# 2_LTE_1.net
KiCad netlist of a schematic drawn in Altium Designer
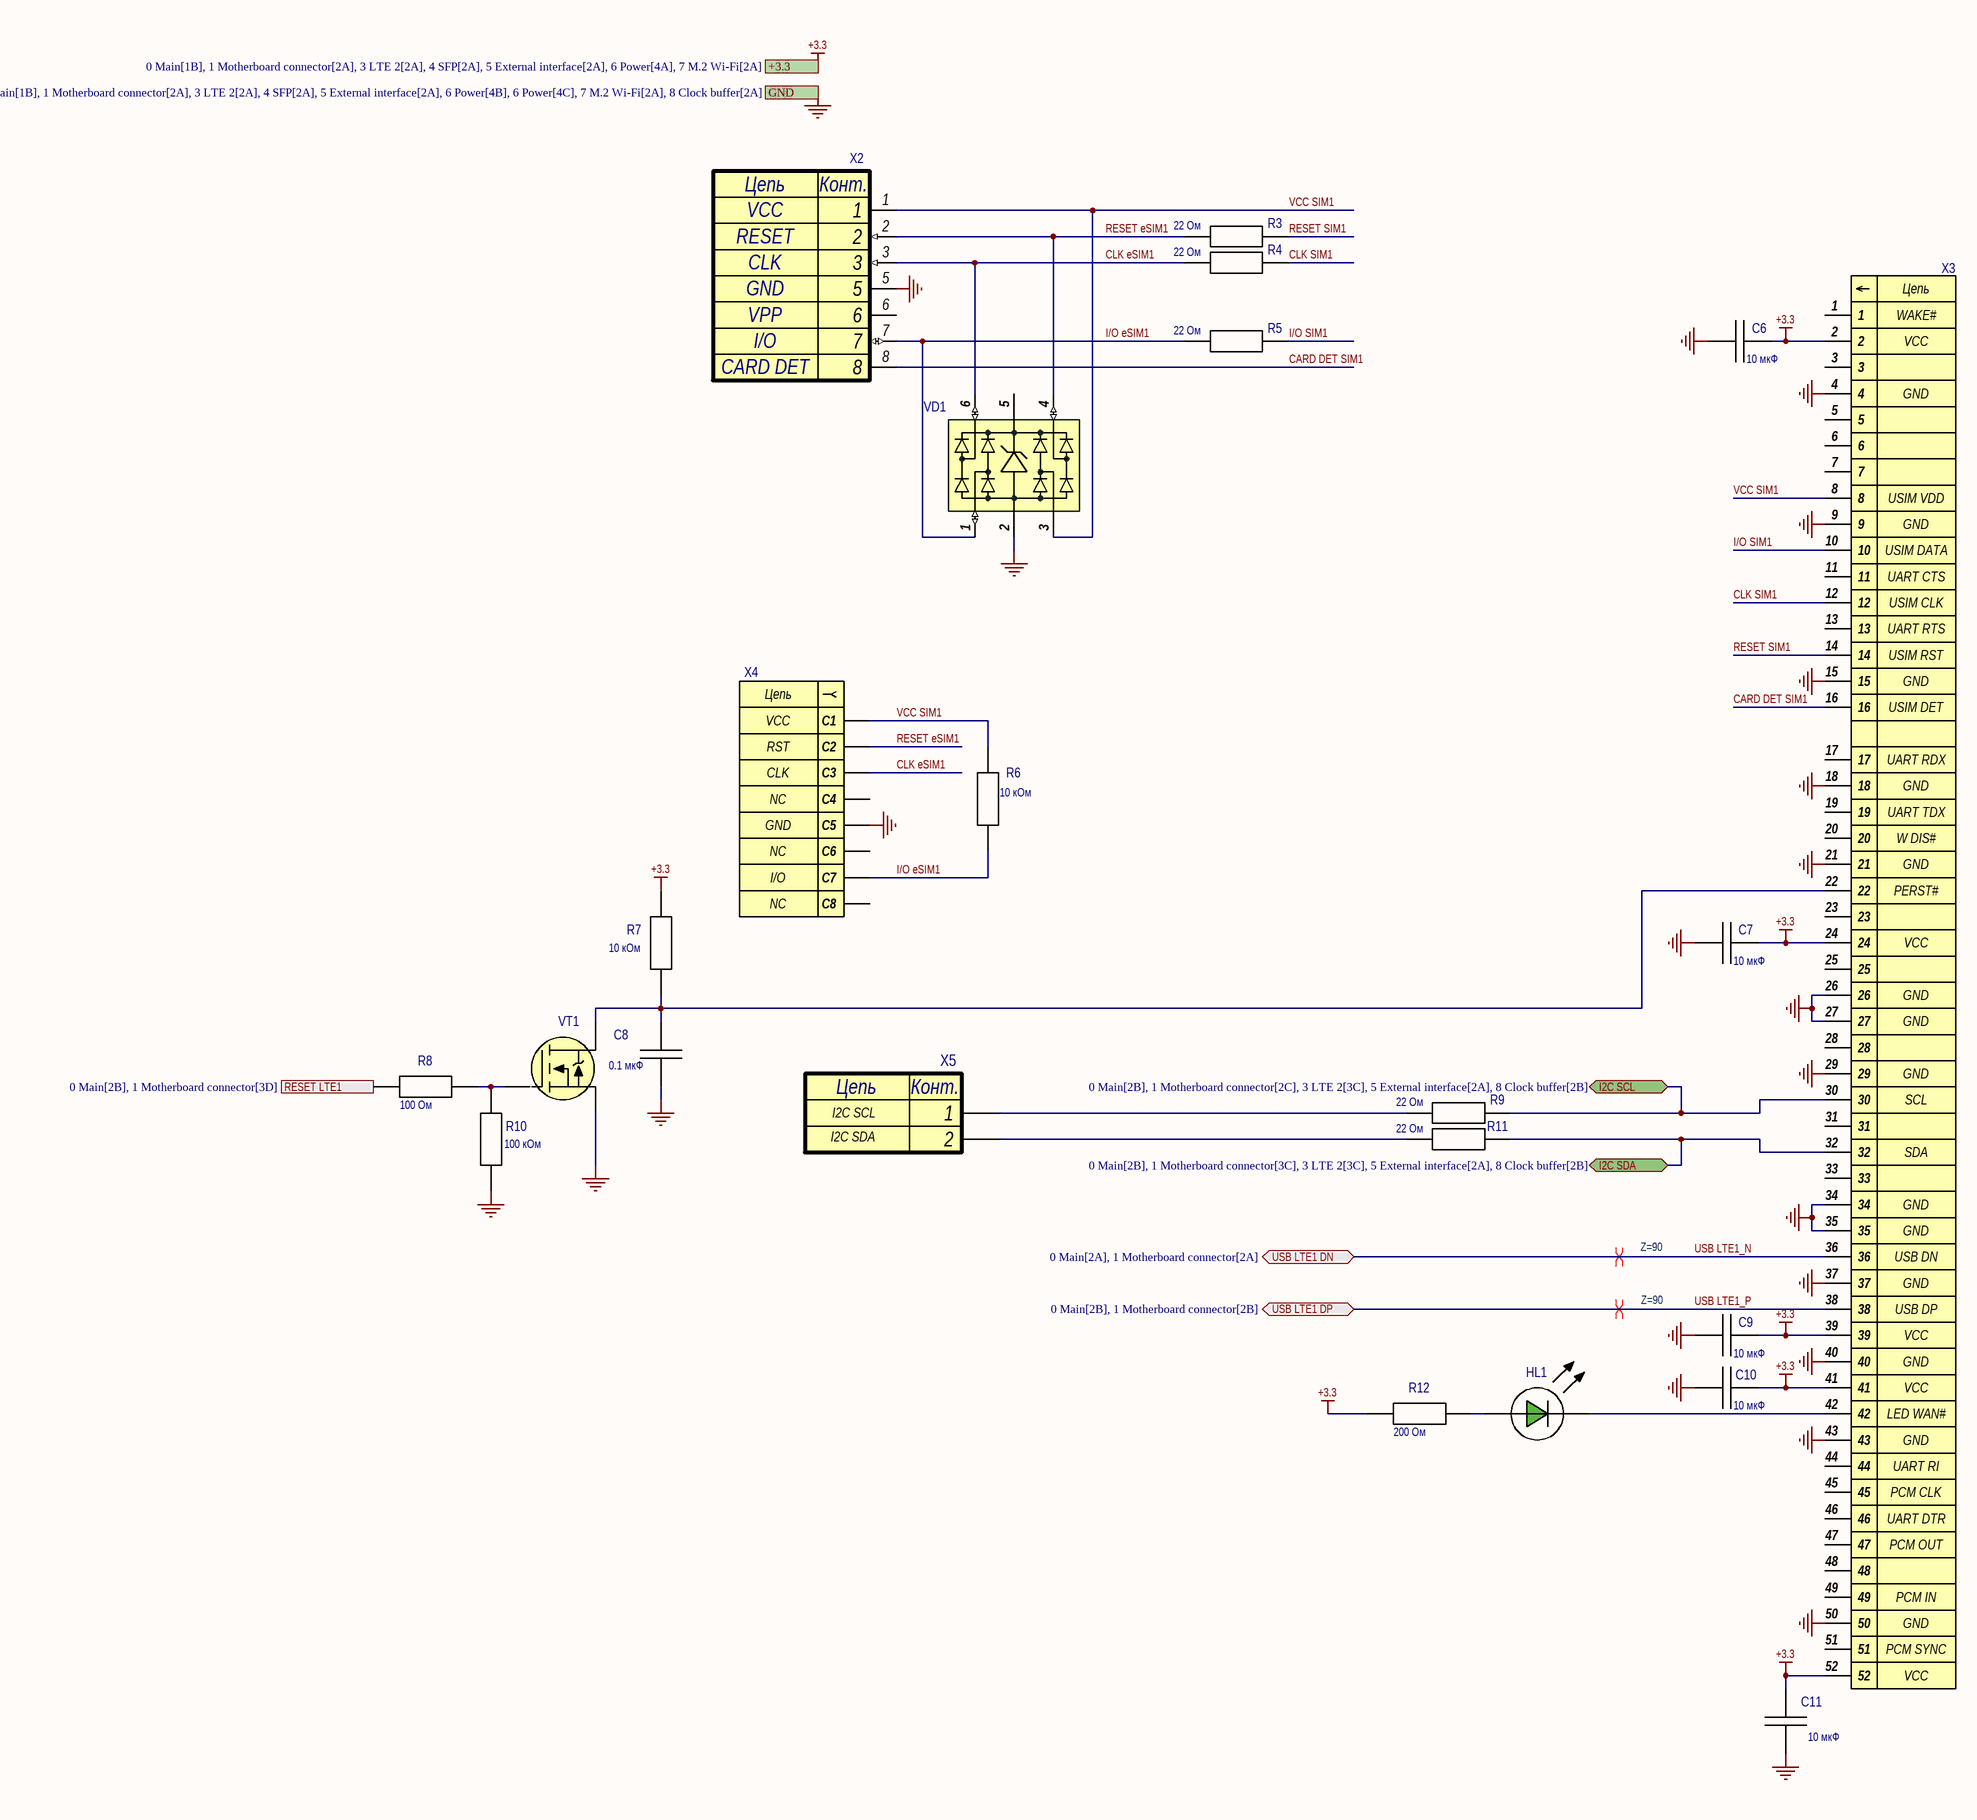
[diagram p0: 2 LTE 1.SchDoc]

(export (version "E")
  (design (tool "Eeschema 10.0.6"))
  (components
    (comp (ref "C6")
      (value "10 мкФ")
      (footprint "CAP_0805")
      (description "Конденсатор CHIP-0805 10 мкФ 16 В 10% X5R")
      (fields
        (field (name "PARTNUMBER") "GRM21BR61C106KE15L")
        (field (name "TOLERANCE") "10%")
        (field (name "AUTOR") "Цислав А.Н.")
      )
      (libsource (lib "Database_Altium") (part "STD_CAP"))
    )
    (comp (ref "C7")
      (value "10 мкФ")
      (footprint "CAP_0805")
      (description "Конденсатор CHIP-0805 10 мкФ 16 В 10% X5R")
      (fields
        (field (name "PARTNUMBER") "GRM21BR61C106KE15L")
        (field (name "TOLERANCE") "10%")
        (field (name "AUTOR") "Цислав А.Н.")
      )
      (libsource (lib "Database_Altium") (part "STD_CAP"))
    )
    (comp (ref "C8")
      (value "0.1 мкФ")
      (footprint "CAP_0402")
      (description "Конденсатор CHIP-0402 0.1 мкФ 50 В 10% X7R")
      (fields
        (field (name "PARTNUMBER") "CC0402KRX7R9BB104")
        (field (name "TOLERANCE") "10%")
        (field (name "AUTOR") "Admin")
      )
      (libsource (lib "Database_Altium") (part "STD_CAP"))
    )
    (comp (ref "C9")
      (value "10 мкФ")
      (footprint "CAP_0805")
      (description "Конденсатор CHIP-0805 10 мкФ 16 В 10% X5R")
      (fields
        (field (name "PARTNUMBER") "GRM21BR61C106KE15L")
        (field (name "TOLERANCE") "10%")
        (field (name "AUTOR") "Цислав А.Н.")
      )
      (libsource (lib "Database_Altium") (part "STD_CAP"))
    )
    (comp (ref "C10")
      (value "10 мкФ")
      (footprint "CAP_0805")
      (description "Конденсатор CHIP-0805 10 мкФ 16 В 10% X5R")
      (fields
        (field (name "PARTNUMBER") "GRM21BR61C106KE15L")
        (field (name "TOLERANCE") "10%")
        (field (name "AUTOR") "Цислав А.Н.")
      )
      (libsource (lib "Database_Altium") (part "STD_CAP"))
    )
    (comp (ref "C11")
      (value "10 мкФ")
      (footprint "CAP_0805")
      (description "Конденсатор CHIP-0805 10 мкФ 16 В 10% X5R")
      (fields
        (field (name "PARTNUMBER") "GRM21BR61C106KE15L")
        (field (name "TOLERANCE") "10%")
        (field (name "AUTOR") "Цислав А.Н.")
      )
      (libsource (lib "Database_Altium") (part "STD_CAP"))
    )
    (comp (ref "HL1")
      (value "APHHS1005CGCK")
      (footprint "LED_0402_GREEN")
      (description "Диод Kingbright 2 В 20 мА")
      (fields (field (name "MANUFACTURER") "Kingbright") (field (name "AUTOR") "Цислав А.Н."))
      (libsource (lib "Database_Altium") (part "APHHS1005CGCK"))
    )
    (comp (ref "R3")
      (value "22 Ом")
      (footprint "RES_0402")
      (description "Резистор CHIP-0402 22 Ом 1%")
      (fields
        (field (name "PARTNUMBER") "RC0402FR-0722RL")
        (field (name "TOLERANCE") "1%")
        (field (name "AUTOR") "Цислав А.Н.")
      )
      (libsource (lib "Database_Altium") (part "STD_RES"))
    )
    (comp (ref "R4")
      (value "22 Ом")
      (footprint "RES_0402")
      (description "Резистор CHIP-0402 22 Ом 1%")
      (fields
        (field (name "PARTNUMBER") "RC0402FR-0722RL")
        (field (name "TOLERANCE") "1%")
        (field (name "AUTOR") "Цислав А.Н.")
      )
      (libsource (lib "Database_Altium") (part "STD_RES"))
    )
    (comp (ref "R5")
      (value "22 Ом")
      (footprint "RES_0402")
      (description "Резистор CHIP-0402 22 Ом 1%")
      (fields
        (field (name "PARTNUMBER") "RC0402FR-0722RL")
        (field (name "TOLERANCE") "1%")
        (field (name "AUTOR") "Цислав А.Н.")
      )
      (libsource (lib "Database_Altium") (part "STD_RES"))
    )
    (comp (ref "R6")
      (value "10 кОм")
      (footprint "RES_0402")
      (description "Резистор CHIP-0402 10 кОм 5%")
      (fields
        (field (name "PARTNUMBER") "RC0402JR-0710KL")
        (field (name "TOLERANCE") "5%")
        (field (name "AUTOR") "Цислав А.Н.")
      )
      (libsource (lib "Database_Altium") (part "STD_RES"))
    )
    (comp (ref "R7")
      (value "10 кОм")
      (footprint "RES_0402")
      (description "Резистор CHIP-0402 10 кОм 5%")
      (fields
        (field (name "PARTNUMBER") "RC0402JR-0710KL")
        (field (name "TOLERANCE") "5%")
        (field (name "AUTOR") "Цислав А.Н.")
      )
      (libsource (lib "Database_Altium") (part "STD_RES"))
    )
    (comp (ref "R8")
      (value "100 Ом")
      (footprint "RES_0402")
      (description "Резистор CHIP-0402 100 Ом 5%")
      (fields
        (field (name "PARTNUMBER") "RC0402JR-07100RL")
        (field (name "TOLERANCE") "5%")
        (field (name "AUTOR") "Цислав А.Н.")
      )
      (libsource (lib "Database_Altium") (part "STD_RES"))
    )
    (comp (ref "R9")
      (value "22 Ом")
      (footprint "RES_0402")
      (description "Резистор CHIP-0402 22 Ом 1%")
      (fields
        (field (name "PARTNUMBER") "RC0402FR-0722RL")
        (field (name "TOLERANCE") "1%")
        (field (name "AUTOR") "Цислав А.Н.")
      )
      (libsource (lib "Database_Altium") (part "STD_RES"))
    )
    (comp (ref "R10")
      (value "100 кОм")
      (footprint "RES_0402")
      (description "Резистор CHIP-0402 100 кОм 5%")
      (fields
        (field (name "PARTNUMBER") "RC0402JR-07100KL")
        (field (name "TOLERANCE") "5%")
        (field (name "AUTOR") "Цислав А.Н.")
      )
      (libsource (lib "Database_Altium") (part "STD_RES"))
    )
    (comp (ref "R11")
      (value "22 Ом")
      (footprint "RES_0402")
      (description "Резистор CHIP-0402 22 Ом 1%")
      (fields
        (field (name "PARTNUMBER") "RC0402FR-0722RL")
        (field (name "TOLERANCE") "1%")
        (field (name "AUTOR") "Цислав А.Н.")
      )
      (libsource (lib "Database_Altium") (part "STD_RES"))
    )
    (comp (ref "R12")
      (value "200 Ом")
      (footprint "RES_0402")
      (description "Резистор CHIP-0402 200 Ом 5%")
      (fields
        (field (name "PARTNUMBER") "RC0402JR-07200RL")
        (field (name "TOLERANCE") "5%")
        (field (name "AUTOR") "Цислав А.Н.")
      )
      (libsource (lib "Database_Altium") (part "STD_RES"))
    )
    (comp (ref "VD1")
      (value "SRV05-4")
      (footprint "SOT-23-6")
      (description "Диод SEMTECH 1.2 В 12 А")
      (fields (field (name "MANUFACTURER") "SEMTECH") (field (name "AUTOR") "Admin"))
      (libsource (lib "Database_Altium") (part "SRV05-4"))
    )
    (comp (ref "VT1")
      (value "2N7002P")
      (footprint "SOT-23-3")
      (description "Микросхема NXP  N-channel Trench MOSFET")
      (fields
        (field (name "VOLTAGE") "60В")
        (field (name "MANUFACTURER") "NXP")
        (field (name "AUTOR") "Admin")
      )
      (libsource (lib "Database_Altium") (part "2N7002P"))
    )
    (comp (ref "X2")
      (value "Sim холдер с детектированием sim-card  и выдвижным держателем SMN-327-KT1B")
      (footprint "SMN-328-ACP7")
      (description "Разъем XunPu SIM")
      (fields
        (field (name "PARTNUMBER") "SMN-328-ACP7")
        (field (name "MANUFACTURER") "XunPu")
        (field (name "CONTACT") "8")
        (field (name "AUTOR") "Admin")
      )
      (libsource (lib "Database_Altium") (part "Sim WITH CD"))
    )
    (comp (ref "X3")
      (value "2041262-1")
      (footprint "2041262-1")
      (description "Разъем TE PCI-E")
      (fields (field (name "MANUFACTURER") "TE") (field (name "CONTACT") "52") (field (name "AUTOR") "Admin"))
      (libsource (lib "Database_Altium") (part "2041262-1"))
    )
    (comp (ref "X4")
      (value "SIM_MFF2")
      (footprint "SIM_MFF2")
      (description "Разъем E - SIM")
      (fields (field (name "MANUFACTURER") "E -") (field (name "CONTACT") "8") (field (name "AUTOR") "Admin"))
      (libsource (lib "Database_Altium") (part "SIM_MFF2"))
    )
    (comp (ref "X5")
      (value "STD_CON2")
      (footprint "PLS-2")
      (description "Разъем NoName PLS")
      (fields
        (field (name "PARTNUMBER") "PLS-2")
        (field (name "MANUFACTURER") "NoName")
        (field (name "CONTACT") "2")
        (field (name "AUTOR") "Admin")
      )
      (libsource (lib "Database_Altium") (part "STD_CON2"))
    )
  )
  (nets
    (net (code "1") (name "+3.3") (class "Default")
      (node (ref "C10") (pin "1") (pinfunction "1_1") (pintype "passive"))
      (node (ref "C11") (pin "1") (pinfunction "1_1") (pintype "passive"))
      (node (ref "C6") (pin "1") (pinfunction "1_1") (pintype "passive"))
      (node (ref "C7") (pin "1") (pinfunction "1_1") (pintype "passive"))
      (node (ref "C9") (pin "1") (pinfunction "1_1") (pintype "passive"))
      (node (ref "R12") (pin "1") (pinfunction "1_1") (pintype "passive"))
      (node (ref "R7") (pin "2") (pinfunction "2_2") (pintype "passive"))
      (node (ref "X3") (pin "2") (pinfunction "2_2") (pintype "passive"))
      (node (ref "X3") (pin "24") (pinfunction "24_24") (pintype "passive"))
      (node (ref "X3") (pin "39") (pinfunction "39_39") (pintype "passive"))
      (node (ref "X3") (pin "41") (pinfunction "41_41") (pintype "passive"))
      (node (ref "X3") (pin "52") (pinfunction "52_52") (pintype "passive"))
    )
    (net (code "2") (name "/CARD DET SIM1") (class "Default")
      (node (ref "X2") (pin "8") (pinfunction "8_8") (pintype "power_in"))
      (node (ref "X3") (pin "16") (pinfunction "16_16") (pintype "passive"))
    )
    (net (code "3") (name "/CLK SIM1") (class "Default")
      (node (ref "R4") (pin "2") (pinfunction "2_2") (pintype "passive"))
      (node (ref "X3") (pin "12") (pinfunction "12_12") (pintype "passive"))
    )
    (net (code "4") (name "/CLK eSIM1") (class "Default")
      (node (ref "R4") (pin "1") (pinfunction "1_1") (pintype "passive"))
      (node (ref "VD1") (pin "6") (pinfunction "6_6") (pintype "bidirectional"))
      (node (ref "X2") (pin "3") (pinfunction "3_3") (pintype "input"))
      (node (ref "X4") (pin "C3") (pinfunction "C3_C3") (pintype "passive"))
    )
    (net (code "5") (name "/I2C SCL") (class "Default")
      (node (ref "R9") (pin "2") (pinfunction "2_2") (pintype "passive"))
      (node (ref "X3") (pin "30") (pinfunction "30_30") (pintype "passive"))
    )
    (net (code "6") (name "/I2C SDA") (class "Default")
      (node (ref "R11") (pin "2") (pinfunction "2_2") (pintype "passive"))
      (node (ref "X3") (pin "32") (pinfunction "32_32") (pintype "passive"))
    )
    (net (code "7") (name "/I{slash}O SIM1") (class "Default")
      (node (ref "R5") (pin "2") (pinfunction "2_2") (pintype "passive"))
      (node (ref "X3") (pin "10") (pinfunction "10_10") (pintype "passive"))
    )
    (net (code "8") (name "/I{slash}O eSIM1") (class "Default")
      (node (ref "R5") (pin "1") (pinfunction "1_1") (pintype "passive"))
      (node (ref "R6") (pin "1") (pinfunction "1_1") (pintype "passive"))
      (node (ref "VD1") (pin "1") (pinfunction "1_1") (pintype "bidirectional"))
      (node (ref "X2") (pin "7") (pinfunction "7_7") (pintype "bidirectional"))
      (node (ref "X4") (pin "C7") (pinfunction "C7_C7") (pintype "passive"))
    )
    (net (code "9") (name "/RESET LTE1") (class "Default")
      (node (ref "R8") (pin "1") (pinfunction "1_1") (pintype "passive"))
    )
    (net (code "10") (name "/RESET SIM1") (class "Default")
      (node (ref "R3") (pin "2") (pinfunction "2_2") (pintype "passive"))
      (node (ref "X3") (pin "14") (pinfunction "14_14") (pintype "passive"))
    )
    (net (code "11") (name "/RESET eSIM1") (class "Default")
      (node (ref "R3") (pin "1") (pinfunction "1_1") (pintype "passive"))
      (node (ref "VD1") (pin "4") (pinfunction "4_4") (pintype "bidirectional"))
      (node (ref "X2") (pin "2") (pinfunction "2_2") (pintype "input"))
      (node (ref "X4") (pin "C2") (pinfunction "C2_C2") (pintype "passive"))
    )
    (net (code "12") (name "/USB LTE1_N") (class "Default")
      (node (ref "X3") (pin "36") (pinfunction "36_36") (pintype "passive"))
    )
    (net (code "13") (name "/USB LTE1_P") (class "Default")
      (node (ref "X3") (pin "38") (pinfunction "38_38") (pintype "passive"))
    )
    (net (code "14") (name "/VCC SIM1") (class "Default")
      (node (ref "R6") (pin "2") (pinfunction "2_2") (pintype "passive"))
      (node (ref "VD1") (pin "3") (pinfunction "3_3") (pintype "passive"))
      (node (ref "X2") (pin "1") (pinfunction "1_1") (pintype "passive"))
      (node (ref "X3") (pin "8") (pinfunction "8_8") (pintype "passive"))
      (node (ref "X4") (pin "C1") (pinfunction "C1_C1") (pintype "passive"))
    )
    (net (code "15") (name "GND") (class "Default")
      (node (ref "C10") (pin "2") (pinfunction "2_2") (pintype "passive"))
      (node (ref "C11") (pin "2") (pinfunction "2_2") (pintype "passive"))
      (node (ref "C6") (pin "2") (pinfunction "2_2") (pintype "passive"))
      (node (ref "C7") (pin "2") (pinfunction "2_2") (pintype "passive"))
      (node (ref "C8") (pin "2") (pinfunction "2_2") (pintype "passive"))
      (node (ref "C9") (pin "2") (pinfunction "2_2") (pintype "passive"))
      (node (ref "R10") (pin "1") (pinfunction "1_1") (pintype "passive"))
      (node (ref "VD1") (pin "2") (pinfunction "2_2") (pintype "passive"))
      (node (ref "VT1") (pin "2") (pinfunction "S_2") (pintype "passive"))
      (node (ref "X2") (pin "5") (pinfunction "5_5") (pintype "passive"))
      (node (ref "X3") (pin "15") (pinfunction "15_15") (pintype "passive"))
      (node (ref "X3") (pin "18") (pinfunction "18_18") (pintype "passive"))
      (node (ref "X3") (pin "21") (pinfunction "21_21") (pintype "passive"))
      (node (ref "X3") (pin "26") (pinfunction "26_26") (pintype "passive"))
      (node (ref "X3") (pin "27") (pinfunction "27_27") (pintype "passive"))
      (node (ref "X3") (pin "29") (pinfunction "29_29") (pintype "passive"))
      (node (ref "X3") (pin "34") (pinfunction "34_34") (pintype "passive"))
      (node (ref "X3") (pin "35") (pinfunction "35_35") (pintype "passive"))
      (node (ref "X3") (pin "37") (pinfunction "37_37") (pintype "passive"))
      (node (ref "X3") (pin "4") (pinfunction "4_4") (pintype "passive"))
      (node (ref "X3") (pin "40") (pinfunction "40_40") (pintype "passive"))
      (node (ref "X3") (pin "43") (pinfunction "43_43") (pintype "passive"))
      (node (ref "X3") (pin "50") (pinfunction "50_50") (pintype "passive"))
      (node (ref "X3") (pin "9") (pinfunction "9_9") (pintype "passive"))
      (node (ref "X4") (pin "C5") (pinfunction "C5_C5") (pintype "passive"))
    )
    (net (code "16") (name "Net-(HL1-A)") (class "Default")
      (node (ref "HL1") (pin "1") (pinfunction "A_1") (pintype "power_in"))
      (node (ref "R12") (pin "2") (pinfunction "2_2") (pintype "passive"))
    )
    (net (code "17") (name "Net-(HL1-K)") (class "Default")
      (node (ref "HL1") (pin "2") (pinfunction "K_2") (pintype "power_in"))
      (node (ref "X3") (pin "42") (pinfunction "42_42") (pintype "passive"))
    )
    (net (code "18") (name "Net-(R9-Pad1)") (class "Default")
      (node (ref "R9") (pin "1") (pinfunction "1_1") (pintype "passive"))
      (node (ref "X5") (pin "1") (pinfunction "1_1") (pintype "passive"))
    )
    (net (code "19") (name "Net-(R11-Pad1)") (class "Default")
      (node (ref "R11") (pin "1") (pinfunction "1_1") (pintype "passive"))
      (node (ref "X5") (pin "2") (pinfunction "2_2") (pintype "passive"))
    )
    (net (code "20") (name "Net-(VT1-D)") (class "Default")
      (node (ref "C8") (pin "1") (pinfunction "1_1") (pintype "passive"))
      (node (ref "R7") (pin "1") (pinfunction "1_1") (pintype "passive"))
      (node (ref "VT1") (pin "3") (pinfunction "D_3") (pintype "passive"))
      (node (ref "X3") (pin "22") (pinfunction "22_22") (pintype "passive"))
    )
    (net (code "21") (name "Net-(VT1-G)") (class "Default")
      (node (ref "R10") (pin "2") (pinfunction "2_2") (pintype "passive"))
      (node (ref "R8") (pin "2") (pinfunction "2_2") (pintype "passive"))
      (node (ref "VT1") (pin "1") (pinfunction "G_1") (pintype "passive"))
    )
    (net (code "22") (name "unconnected-(VD1-Pad5)") (class "Default")
      (node (ref "VD1") (pin "5") (pinfunction "5_5") (pintype "passive"))
    )
    (net (code "23") (name "unconnected-(X2-Pad6)") (class "Default")
      (node (ref "X2") (pin "6") (pinfunction "6_6") (pintype "power_in"))
    )
    (net (code "24") (name "unconnected-(X3-Pad1)") (class "Default")
      (node (ref "X3") (pin "1") (pinfunction "1_1") (pintype "passive"))
    )
    (net (code "25") (name "unconnected-(X3-Pad3)") (class "Default")
      (node (ref "X3") (pin "3") (pinfunction "3_3") (pintype "passive"))
    )
    (net (code "26") (name "unconnected-(X3-Pad5)") (class "Default")
      (node (ref "X3") (pin "5") (pinfunction "5_5") (pintype "passive"))
    )
    (net (code "27") (name "unconnected-(X3-Pad6)") (class "Default")
      (node (ref "X3") (pin "6") (pinfunction "6_6") (pintype "passive"))
    )
    (net (code "28") (name "unconnected-(X3-Pad7)") (class "Default")
      (node (ref "X3") (pin "7") (pinfunction "7_7") (pintype "passive"))
    )
    (net (code "29") (name "unconnected-(X3-Pad11)") (class "Default")
      (node (ref "X3") (pin "11") (pinfunction "11_11") (pintype "passive"))
    )
    (net (code "30") (name "unconnected-(X3-Pad13)") (class "Default")
      (node (ref "X3") (pin "13") (pinfunction "13_13") (pintype "passive"))
    )
    (net (code "31") (name "unconnected-(X3-Pad17)") (class "Default")
      (node (ref "X3") (pin "17") (pinfunction "17_17") (pintype "passive"))
    )
    (net (code "32") (name "unconnected-(X3-Pad19)") (class "Default")
      (node (ref "X3") (pin "19") (pinfunction "19_19") (pintype "passive"))
    )
    (net (code "33") (name "unconnected-(X3-Pad20)") (class "Default")
      (node (ref "X3") (pin "20") (pinfunction "20_20") (pintype "passive"))
    )
    (net (code "34") (name "unconnected-(X3-Pad23)") (class "Default")
      (node (ref "X3") (pin "23") (pinfunction "23_23") (pintype "passive"))
    )
    (net (code "35") (name "unconnected-(X3-Pad25)") (class "Default")
      (node (ref "X3") (pin "25") (pinfunction "25_25") (pintype "passive"))
    )
    (net (code "36") (name "unconnected-(X3-Pad28)") (class "Default")
      (node (ref "X3") (pin "28") (pinfunction "28_28") (pintype "passive"))
    )
    (net (code "37") (name "unconnected-(X3-Pad31)") (class "Default")
      (node (ref "X3") (pin "31") (pinfunction "31_31") (pintype "passive"))
    )
    (net (code "38") (name "unconnected-(X3-Pad33)") (class "Default")
      (node (ref "X3") (pin "33") (pinfunction "33_33") (pintype "passive"))
    )
    (net (code "39") (name "unconnected-(X3-Pad44)") (class "Default")
      (node (ref "X3") (pin "44") (pinfunction "44_44") (pintype "passive"))
    )
    (net (code "40") (name "unconnected-(X3-Pad45)") (class "Default")
      (node (ref "X3") (pin "45") (pinfunction "45_45") (pintype "passive"))
    )
    (net (code "41") (name "unconnected-(X3-Pad46)") (class "Default")
      (node (ref "X3") (pin "46") (pinfunction "46_46") (pintype "passive"))
    )
    (net (code "42") (name "unconnected-(X3-Pad47)") (class "Default")
      (node (ref "X3") (pin "47") (pinfunction "47_47") (pintype "passive"))
    )
    (net (code "43") (name "unconnected-(X3-Pad48)") (class "Default")
      (node (ref "X3") (pin "48") (pinfunction "48_48") (pintype "passive"))
    )
    (net (code "44") (name "unconnected-(X3-Pad49)") (class "Default")
      (node (ref "X3") (pin "49") (pinfunction "49_49") (pintype "passive"))
    )
    (net (code "45") (name "unconnected-(X3-Pad51)") (class "Default")
      (node (ref "X3") (pin "51") (pinfunction "51_51") (pintype "passive"))
    )
    (net (code "46") (name "unconnected-(X4-PadC4)") (class "Default")
      (node (ref "X4") (pin "C4") (pinfunction "C4_C4") (pintype "passive"))
    )
    (net (code "47") (name "unconnected-(X4-PadC6)") (class "Default")
      (node (ref "X4") (pin "C6") (pinfunction "C6_C6") (pintype "passive"))
    )
    (net (code "48") (name "unconnected-(X4-PadC8)") (class "Default")
      (node (ref "X4") (pin "C8") (pinfunction "C8_C8") (pintype "passive"))
    )
  )
)
